# SNES_AddOn1Chip_SMD.net
KiCad netlist of a schematic drawn in EAGLE
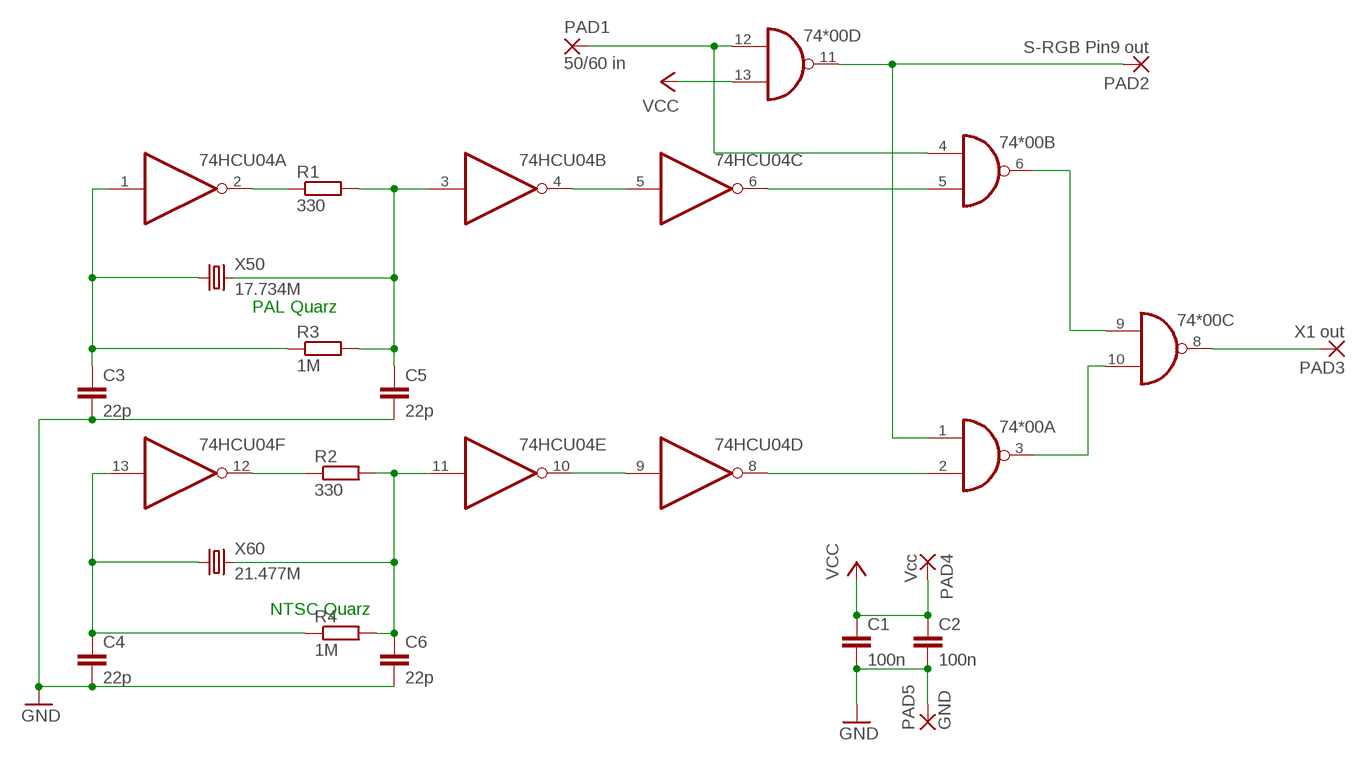
[diagram p0: schematic, sheet 1]

(export (version "E")
  (design (tool "Eeschema 10.0.6"))
  (components
    (comp (ref "74*00")
      (value "7400D")
      (footprint "eagle-import:SO14")
      (libsource (lib "eagle-import") (part "7400D"))
    )
    (comp (ref "74HCU04")
      (value "74HC04D")
      (footprint "eagle-import:SO14")
      (libsource (lib "eagle-import") (part "7404DHC"))
    )
    (comp (ref "C1")
      (value "100n")
      (footprint "eagle-import:Z0805")
      (libsource (lib "eagle-import") (part "C0805"))
    )
    (comp (ref "C2")
      (value "100n")
      (footprint "eagle-import:Z0805")
      (libsource (lib "eagle-import") (part "C0805"))
    )
    (comp (ref "C3")
      (value "22p")
      (footprint "eagle-import:Z0805")
      (libsource (lib "eagle-import") (part "C0805"))
    )
    (comp (ref "C4")
      (value "22p")
      (footprint "eagle-import:Z0805")
      (libsource (lib "eagle-import") (part "C0805"))
    )
    (comp (ref "C5")
      (value "22p")
      (footprint "eagle-import:Z0805")
      (libsource (lib "eagle-import") (part "C0805"))
    )
    (comp (ref "C6")
      (value "22p")
      (footprint "eagle-import:Z0805")
      (libsource (lib "eagle-import") (part "C0805"))
    )
    (comp (ref "PAD1")
      (value "50/60 in")
      (footprint "eagle-import:SMD1,27-2,54")
      (libsource (lib "eagle-import") (part "SMD2"))
    )
    (comp (ref "PAD2")
      (value "S-RGB Pin9 out")
      (footprint "eagle-import:SMD1,27-2,54")
      (libsource (lib "eagle-import") (part "SMD2"))
    )
    (comp (ref "PAD3")
      (value "X1 out")
      (footprint "eagle-import:SMD1,27-2,54")
      (libsource (lib "eagle-import") (part "SMD2"))
    )
    (comp (ref "PAD4")
      (value "Vcc")
      (footprint "eagle-import:SMD2,54-5,08")
      (libsource (lib "eagle-import") (part "SMD5"))
    )
    (comp (ref "PAD5")
      (value "GND")
      (footprint "eagle-import:SMD2,54-5,08")
      (libsource (lib "eagle-import") (part "SMD5"))
    )
    (comp (ref "R1")
      (value "330")
      (footprint "eagle-import:Z0805")
      (libsource (lib "eagle-import") (part "R0805"))
    )
    (comp (ref "R2")
      (value "330")
      (footprint "eagle-import:Z0805")
      (libsource (lib "eagle-import") (part "R0805"))
    )
    (comp (ref "R3")
      (value "1M")
      (footprint "eagle-import:Z0805")
      (libsource (lib "eagle-import") (part "R0805"))
    )
    (comp (ref "R4")
      (value "1M")
      (footprint "eagle-import:Z0805")
      (libsource (lib "eagle-import") (part "R0805"))
    )
    (comp (ref "X50")
      (value "17.734M")
      (footprint "eagle-import:MY_SMD_CRYSTAL2")
      (libsource (lib "eagle-import") (part "MY_CRYSTALS"))
    )
    (comp (ref "X60")
      (value "21.477M")
      (footprint "eagle-import:MY_SMD_CRYSTAL2")
      (libsource (lib "eagle-import") (part "MY_CRYSTALS"))
    )
  )
  (nets
    (net (code "1") (name "GND") (class "Default")
      (node (ref "C1") (pin "2") (pinfunction "2_2") (pintype "passive"))
      (node (ref "C2") (pin "2") (pinfunction "2_2") (pintype "passive"))
      (node (ref "C3") (pin "2") (pinfunction "2_2") (pintype "passive"))
      (node (ref "C4") (pin "2") (pinfunction "2_2") (pintype "passive"))
      (node (ref "C5") (pin "2") (pinfunction "2_2") (pintype "passive"))
      (node (ref "C6") (pin "2") (pinfunction "2_2") (pintype "passive"))
      (node (ref "PAD5") (pin "1") (pinfunction "P_1") (pintype "passive"))
    )
    (net (code "2") (name "Net-(74*00A-I0)") (class "Default")
      (node (ref "74*00") (pin "1") (pinfunction "I0_1") (pintype "input"))
      (node (ref "74*00") (pin "11") (pinfunction "O_11") (pintype "output"))
      (node (ref "PAD2") (pin "1") (pinfunction "P_1") (pintype "passive"))
    )
    (net (code "3") (name "Net-(74*00A-I1)") (class "Default")
      (node (ref "74*00") (pin "2") (pinfunction "I1_2") (pintype "input"))
      (node (ref "74HCU04") (pin "8") (pinfunction "O_8") (pintype "output"))
    )
    (net (code "4") (name "Net-(74*00A-O)") (class "Default")
      (node (ref "74*00") (pin "10") (pinfunction "I1_10") (pintype "input"))
      (node (ref "74*00") (pin "3") (pinfunction "O_3") (pintype "output"))
    )
    (net (code "5") (name "Net-(74*00B-I0)") (class "Default")
      (node (ref "74*00") (pin "12") (pinfunction "I0_12") (pintype "input"))
      (node (ref "74*00") (pin "4") (pinfunction "I0_4") (pintype "input"))
      (node (ref "PAD1") (pin "1") (pinfunction "P_1") (pintype "passive"))
    )
    (net (code "6") (name "Net-(74*00B-I1)") (class "Default")
      (node (ref "74*00") (pin "5") (pinfunction "I1_5") (pintype "input"))
      (node (ref "74HCU04") (pin "6") (pinfunction "O_6") (pintype "output"))
    )
    (net (code "7") (name "Net-(74*00B-O)") (class "Default")
      (node (ref "74*00") (pin "6") (pinfunction "O_6") (pintype "output"))
      (node (ref "74*00") (pin "9") (pinfunction "I0_9") (pintype "input"))
    )
    (net (code "8") (name "Net-(74*00C-O)") (class "Default")
      (node (ref "74*00") (pin "8") (pinfunction "O_8") (pintype "output"))
      (node (ref "PAD3") (pin "1") (pinfunction "P_1") (pintype "passive"))
    )
    (net (code "9") (name "Net-(74HCU04A-I)") (class "Default")
      (node (ref "74HCU04") (pin "1") (pinfunction "I_1") (pintype "input"))
      (node (ref "C3") (pin "1") (pinfunction "1_1") (pintype "passive"))
      (node (ref "R3") (pin "1") (pinfunction "1_1") (pintype "passive"))
      (node (ref "X50") (pin "1") (pinfunction "1_1") (pintype "passive"))
    )
    (net (code "10") (name "Net-(74HCU04A-O)") (class "Default")
      (node (ref "74HCU04") (pin "2") (pinfunction "O_2") (pintype "output"))
      (node (ref "R1") (pin "1") (pinfunction "1_1") (pintype "passive"))
    )
    (net (code "11") (name "Net-(74HCU04B-I)") (class "Default")
      (node (ref "74HCU04") (pin "3") (pinfunction "I_3") (pintype "input"))
      (node (ref "C5") (pin "1") (pinfunction "1_1") (pintype "passive"))
      (node (ref "R1") (pin "2") (pinfunction "2_2") (pintype "passive"))
      (node (ref "R3") (pin "2") (pinfunction "2_2") (pintype "passive"))
      (node (ref "X50") (pin "2") (pinfunction "2_2") (pintype "passive"))
    )
    (net (code "12") (name "Net-(74HCU04B-O)") (class "Default")
      (node (ref "74HCU04") (pin "4") (pinfunction "O_4") (pintype "output"))
      (node (ref "74HCU04") (pin "5") (pinfunction "I_5") (pintype "input"))
    )
    (net (code "13") (name "Net-(74HCU04D-I)") (class "Default")
      (node (ref "74HCU04") (pin "10") (pinfunction "O_10") (pintype "output"))
      (node (ref "74HCU04") (pin "9") (pinfunction "I_9") (pintype "input"))
    )
    (net (code "14") (name "Net-(74HCU04E-I)") (class "Default")
      (node (ref "74HCU04") (pin "11") (pinfunction "I_11") (pintype "input"))
      (node (ref "C6") (pin "1") (pinfunction "1_1") (pintype "passive"))
      (node (ref "R2") (pin "2") (pinfunction "2_2") (pintype "passive"))
      (node (ref "R4") (pin "2") (pinfunction "2_2") (pintype "passive"))
      (node (ref "X60") (pin "2") (pinfunction "2_2") (pintype "passive"))
    )
    (net (code "15") (name "Net-(74HCU04F-I)") (class "Default")
      (node (ref "74HCU04") (pin "13") (pinfunction "I_13") (pintype "input"))
      (node (ref "C4") (pin "1") (pinfunction "1_1") (pintype "passive"))
      (node (ref "R4") (pin "1") (pinfunction "1_1") (pintype "passive"))
      (node (ref "X60") (pin "1") (pinfunction "1_1") (pintype "passive"))
    )
    (net (code "16") (name "Net-(74HCU04F-O)") (class "Default")
      (node (ref "74HCU04") (pin "12") (pinfunction "O_12") (pintype "output"))
      (node (ref "R2") (pin "1") (pinfunction "1_1") (pintype "passive"))
    )
    (net (code "17") (name "VCC") (class "Default")
      (node (ref "74*00") (pin "13") (pinfunction "I1_13") (pintype "input"))
      (node (ref "C1") (pin "1") (pinfunction "1_1") (pintype "passive"))
      (node (ref "C2") (pin "1") (pinfunction "1_1") (pintype "passive"))
      (node (ref "PAD4") (pin "1") (pinfunction "P_1") (pintype "passive"))
    )
  )
)
